# AUDIO_MIC.net
KiCad netlist of a schematic drawn in Altium Designer
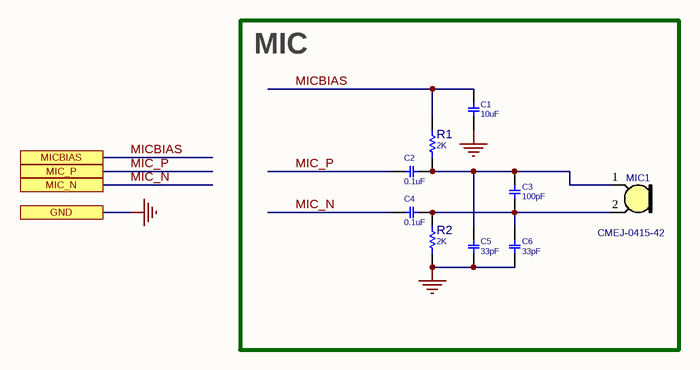
[diagram p0: AUDIO_MIC.SchDoc]

(export (version "E")
  (design (tool "Eeschema 10.0.6"))
  (components
    (comp (ref "C1")
      (value "10uF")
      (footprint "C0402")
      (description "CAP, MLCC")
      (fields (field (name "MANF_P#") "GRM155R60J106ME15") (field (name "MANF") "Murata"))
      (libsource (lib "mlcc_smd_passive") (part "CAP_SMD_MLCC"))
    )
    (comp (ref "C2")
      (value "0.1uF")
      (footprint "C0402")
      (description "CAP, MLCC")
      (fields (field (name "MANF_P#") "GRM155R71H104KE14D") (field (name "MANF") "Murata"))
      (libsource (lib "mlcc_smd_passive") (part "CAP_SMD_MLCC_100n50TDK"))
    )
    (comp (ref "C3")
      (value "100pF")
      (footprint "C0402")
      (description "CAP, MLCC, 100nF, 50V, X7R, 10%, 0402C")
      (fields (field (name "MANF_P#") "GCM155R71H104KE02D") (field (name "MANF") "Murata"))
      (libsource (lib "mlcc_smd_passive") (part "CAP_SMD_MLCC_100n50TDK"))
    )
    (comp (ref "C4")
      (value "0.1uF")
      (footprint "C0402")
      (description "CAP, MLCC")
      (fields (field (name "MANF_P#") "GRM155R71H104KE14D") (field (name "MANF") "Murata"))
      (libsource (lib "mlcc_smd_passive") (part "CAP_SMD_MLCC_100n50TDK"))
    )
    (comp (ref "C5")
      (value "33pF")
      (footprint "C0402")
      (description "CAP, MLCC, 100nF, 50V, X7R, 10%, 0402C")
      (fields (field (name "MANF_P#") "GCM155R71H104KE02D") (field (name "MANF") "Murata"))
      (libsource (lib "mlcc_smd_passive") (part "CAP_SMD_MLCC_100n50TDK"))
    )
    (comp (ref "C6")
      (value "33pF")
      (footprint "C0402")
      (description "CAP, MLCC, 100nF, 50V, X7R, 10%, 0402C")
      (fields (field (name "MANF_P#") "GCM155R71H104KE02D") (field (name "MANF") "Murata"))
      (libsource (lib "mlcc_smd_passive") (part "CAP_SMD_MLCC_100n50TDK"))
    )
    (comp (ref "MIC1")
      (value "CMEJ-0415-42")
      (footprint "MIC_C4")
      (description "MICROPHONE, OMNI 4X1.5mm 2.2k -42DB")
      (fields (field (name "MANF") "CUI") (field (name "MANF_P#") "CMEJ-0415-42-P"))
      (libsource (lib "audio_mic_spk") (part "MIC_CMEJ-0415-42"))
    )
    (comp (ref "R1")
      (value "2K")
      (footprint "R0402")
      (description "RESISTOR, SMD")
      (libsource (lib "passive_res_smd") (part "RES_SMD"))
    )
    (comp (ref "R2")
      (value "2K")
      (footprint "R0402")
      (description "RESISTOR, SMD")
      (libsource (lib "passive_res_smd") (part "RES_SMD"))
    )
  )
  (nets
    (net (code "1") (name "/MICBIAS") (class "Default")
      (node (ref "C1") (pin "1") (pinfunction "1_1") (pintype "passive"))
      (node (ref "R1") (pin "1") (pinfunction "1_1") (pintype "passive"))
    )
    (net (code "2") (name "/MIC_N") (class "Default")
      (node (ref "C4") (pin "1") (pinfunction "1_1") (pintype "passive"))
    )
    (net (code "3") (name "/MIC_P") (class "Default")
      (node (ref "C2") (pin "1") (pinfunction "1_1") (pintype "passive"))
    )
    (net (code "4") (name "GND") (class "Default")
      (node (ref "C1") (pin "2") (pinfunction "2_2") (pintype "passive"))
      (node (ref "C5") (pin "1") (pinfunction "1_1") (pintype "passive"))
      (node (ref "C6") (pin "1") (pinfunction "1_1") (pintype "passive"))
      (node (ref "R2") (pin "1") (pinfunction "1_1") (pintype "passive"))
    )
    (net (code "5") (name "Net-(MIC1-GND)") (class "Default")
      (node (ref "C3") (pin "1") (pinfunction "1_1") (pintype "passive"))
      (node (ref "C4") (pin "2") (pinfunction "2_2") (pintype "passive"))
      (node (ref "C6") (pin "2") (pinfunction "2_2") (pintype "passive"))
      (node (ref "MIC1") (pin "2") (pinfunction "GND_2") (pintype "passive"))
      (node (ref "R2") (pin "2") (pinfunction "2_2") (pintype "passive"))
    )
    (net (code "6") (name "Net-(MIC1-OUT)") (class "Default")
      (node (ref "C2") (pin "2") (pinfunction "2_2") (pintype "passive"))
      (node (ref "C3") (pin "2") (pinfunction "2_2") (pintype "passive"))
      (node (ref "C5") (pin "2") (pinfunction "2_2") (pintype "passive"))
      (node (ref "MIC1") (pin "1") (pinfunction "OUT_1") (pintype "passive"))
      (node (ref "R1") (pin "2") (pinfunction "2_2") (pintype "passive"))
    )
  )
)
